# Qwiic_Adaptive_Switch_Input1_1.net
KiCad netlist of a schematic drawn in EAGLE
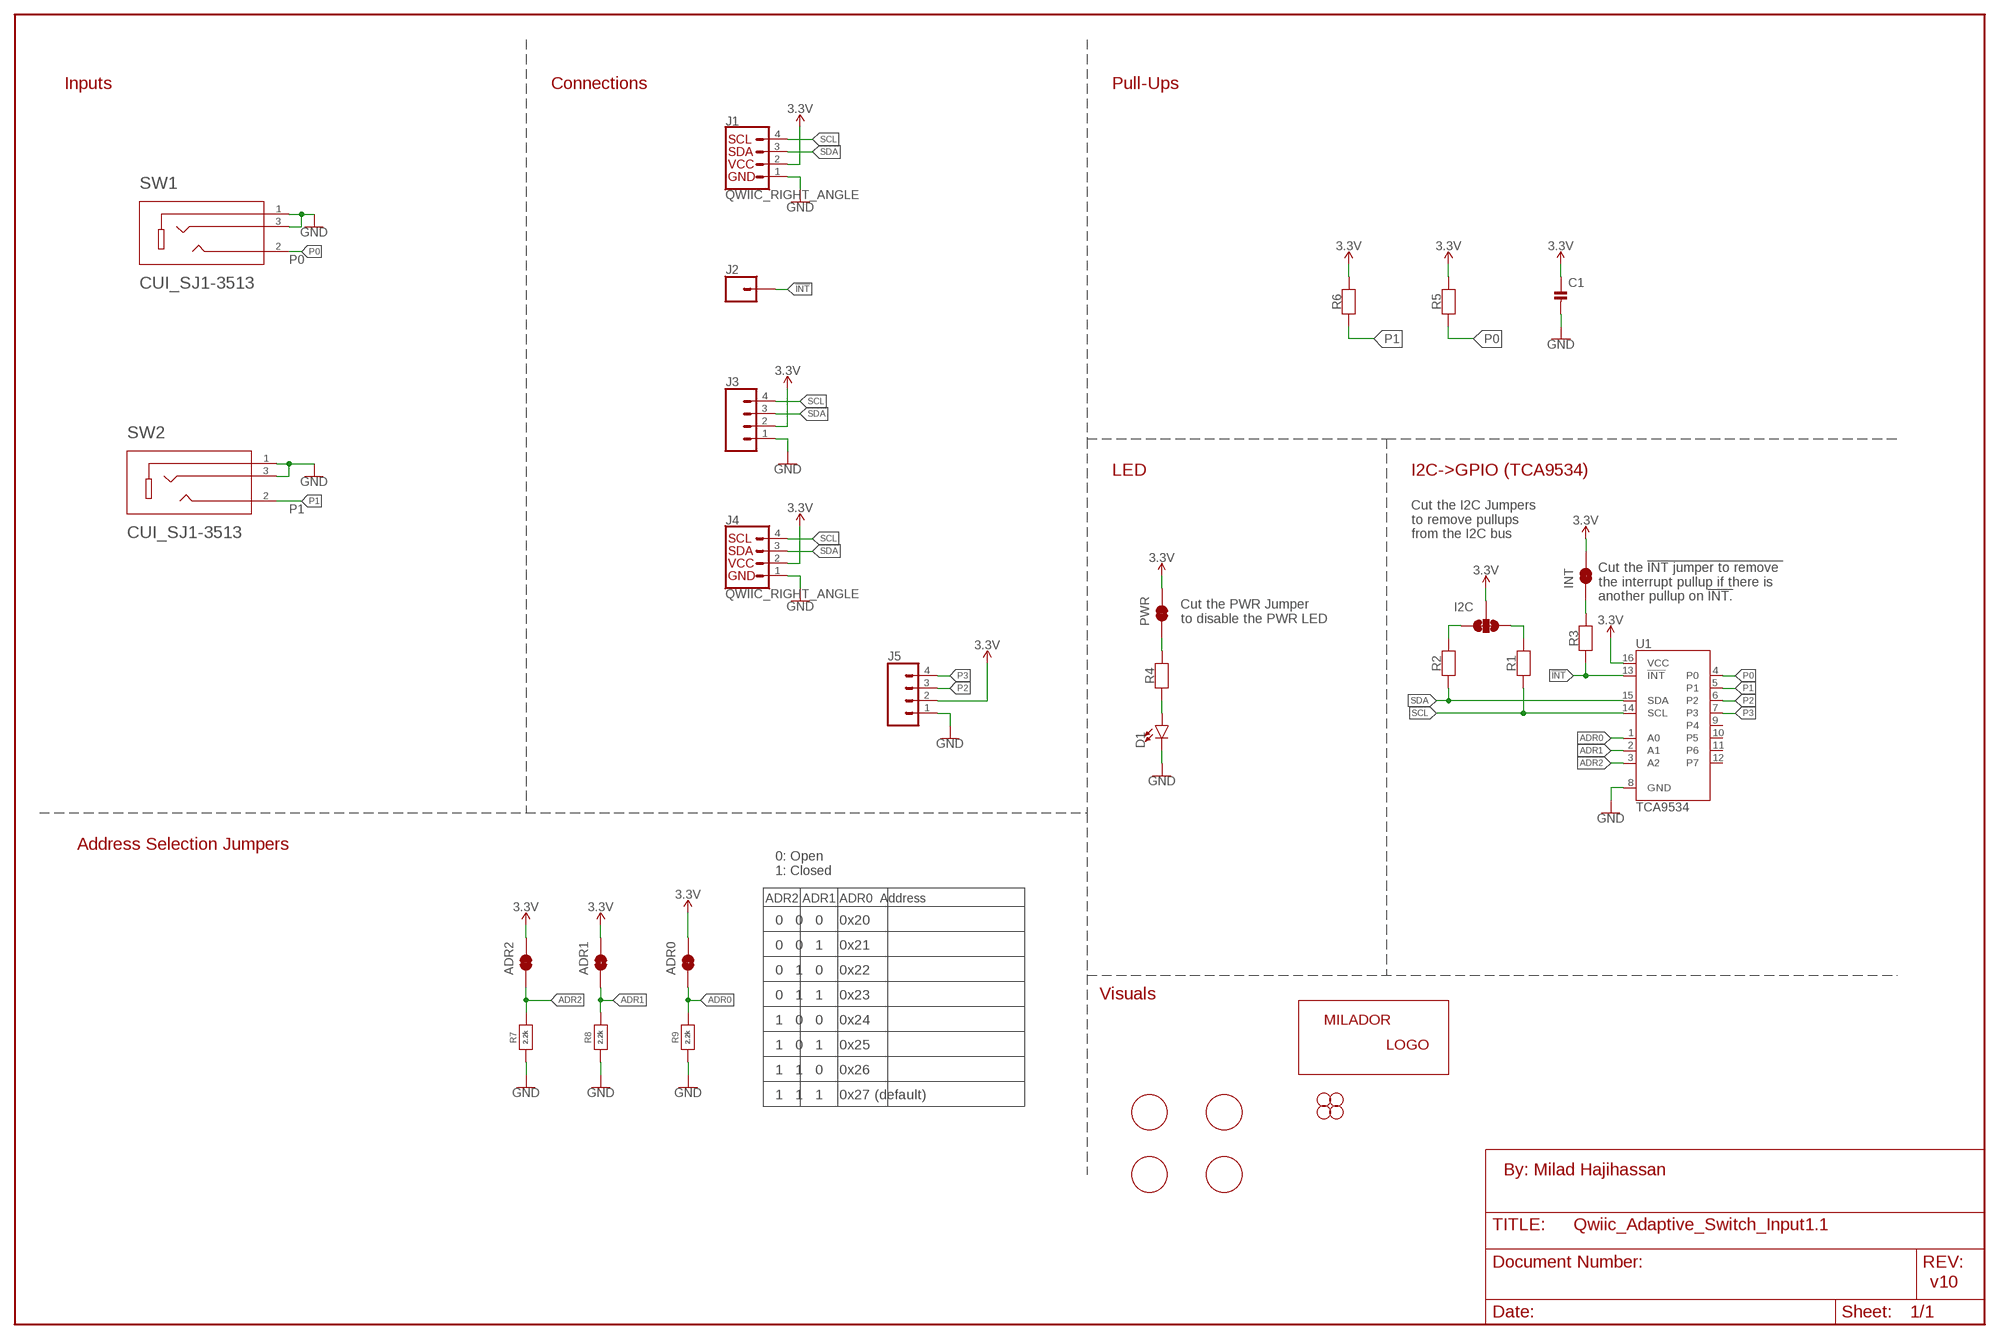
[diagram p0: schematic, sheet 1]

(export (version "E")
  (design (tool "Eeschema 10.0.6"))
  (components
    (comp (ref "ADR0")
      (value "JUMPERS-SMT_2_NC_TRACE_SILK")
      (footprint "eagle-import:JUMPERS_SMT-JUMPER_2_NC_TRACE_SILK")
      (libsource (lib "eagle-import") (part "JUMPERS-SMT_2_NC_TRACE_SILK"))
    )
    (comp (ref "ADR1")
      (value "JUMPERS-SMT_2_NC_TRACE_SILK")
      (footprint "eagle-import:JUMPERS_SMT-JUMPER_2_NC_TRACE_SILK")
      (libsource (lib "eagle-import") (part "JUMPERS-SMT_2_NC_TRACE_SILK"))
    )
    (comp (ref "ADR2")
      (value "JUMPERS-SMT_2_NC_TRACE_SILK")
      (footprint "eagle-import:JUMPERS_SMT-JUMPER_2_NC_TRACE_SILK")
      (libsource (lib "eagle-import") (part "JUMPERS-SMT_2_NC_TRACE_SILK"))
    )
    (comp (ref "C1")
      (value "0.1uF")
      (footprint "eagle-import:0805-MP")
      (libsource (lib "eagle-import") (part "CAP_CERAMIC-0805-MP"))
    )
    (comp (ref "D1")
      (value "RED")
      (footprint "eagle-import:CHIPLED_0805_NOOUTLINE")
      (libsource (lib "eagle-import") (part "LED0805_NOOUTLINE"))
    )
    (comp (ref "H1")
      (value "STAND-OFF-3.3")
      (footprint "eagle-import:STAND-OFF-3.3")
      (libsource (lib "eagle-import") (part "STAND-OFF-3.3"))
    )
    (comp (ref "H2")
      (value "STAND-OFF-3.3")
      (footprint "eagle-import:STAND-OFF-3.3")
      (libsource (lib "eagle-import") (part "STAND-OFF-3.3"))
    )
    (comp (ref "I2C")
      (value "JUMPERS_JUMPER-SMT_3_2-NC_TRACE_SILK")
      (footprint "eagle-import:JUMPERS_SMT-JUMPER_3_2-NC_TRACE_SILK")
      (libsource (lib "eagle-import") (part "JUMPERS_JUMPER-SMT_3_2-NC_TRACE_SILK"))
    )
    (comp (ref "INT")
      (value "JUMPERS-SMT_2_NC_TRACE_SILK")
      (footprint "eagle-import:JUMPERS_SMT-JUMPER_2_NC_TRACE_SILK")
      (libsource (lib "eagle-import") (part "JUMPERS-SMT_2_NC_TRACE_SILK"))
    )
    (comp (ref "J1")
      (value "QWIIC_RIGHT_ANGLE")
      (footprint "eagle-import:CONNECTORS_JST04_1MM_RA")
      (fields (field (name "PROD_ID") "CONN-13694"))
      (libsource (lib "eagle-import") (part "QWIIC_CONNECTORSJS-1MM"))
    )
    (comp (ref "J2")
      (value "CONNECTORS_CONN_01PTH_NO_SILK_YES_STOP")
      (footprint "eagle-import:CONNECTORS_1X01_NO_SILK")
      (libsource (lib "eagle-import") (part "CONNECTORS_CONN_01PTH_NO_SILK_YES_STOP"))
    )
    (comp (ref "J3")
      (value "CONNECTORS_CONN_041X04_NO_SILK")
      (footprint "eagle-import:CONNECTORS_1X04_NO_SILK")
      (libsource (lib "eagle-import") (part "CONNECTORS_CONN_041X04_NO_SILK"))
    )
    (comp (ref "J4")
      (value "QWIIC_RIGHT_ANGLE")
      (footprint "eagle-import:CONNECTORS_JST04_1MM_RA")
      (fields (field (name "PROD_ID") "CONN-13694"))
      (libsource (lib "eagle-import") (part "QWIIC_CONNECTORSJS-1MM"))
    )
    (comp (ref "J5")
      (value "CONNECTORS_CONN_041X04_NO_SILK")
      (footprint "eagle-import:CONNECTORS_1X04_NO_SILK")
      (libsource (lib "eagle-import") (part "CONNECTORS_CONN_041X04_NO_SILK"))
    )
    (comp (ref "JP3")
      (value "STAND-OFF-3.3")
      (footprint "eagle-import:STAND-OFF-3.3")
      (libsource (lib "eagle-import") (part "STAND-OFF-3.3"))
    )
    (comp (ref "JP4")
      (value "STAND-OFF-3.3")
      (footprint "eagle-import:STAND-OFF-3.3")
      (libsource (lib "eagle-import") (part "STAND-OFF-3.3"))
    )
    (comp (ref "LABEL_2")
      (value "MILADOR-SWITCH-NAME-SW1")
      (footprint "eagle-import:SWITCH-SW1")
      (libsource (lib "eagle-import") (part "MILADOR-SWITCH-NAME-SW1"))
    )
    (comp (ref "LABEL_3")
      (value "MILADOR-SWITCH-NAME-SW2")
      (footprint "eagle-import:SWITCH-SW2")
      (libsource (lib "eagle-import") (part "MILADOR-SWITCH-NAME-SW2"))
    )
    (comp (ref "LABEL_9")
      (value "MILADOR-SWITCH-NAME-SW-INPUT")
      (footprint "eagle-import:SWITCH-INPUT")
      (libsource (lib "eagle-import") (part "MILADOR-SWITCH-NAME-SW-INPUT"))
    )
    (comp (ref "LABEL_14")
      (value "MILADOR-LOGO-")
      (footprint "eagle-import:MILADOR_LOGO1")
      (libsource (lib "eagle-import") (part "MILADOR-LOGO-"))
    )
    (comp (ref "LABEL_18")
      (value "MILADOR-SWITCH-NAME-SW-INPUT")
      (footprint "eagle-import:SWITCH-INPUT")
      (libsource (lib "eagle-import") (part "MILADOR-SWITCH-NAME-SW-INPUT"))
    )
    (comp (ref "PWR")
      (value "JUMPERS-SMT_2_NC_TRACE_SILK")
      (footprint "eagle-import:JUMPERS_SMT-JUMPER_2_NC_TRACE_SILK")
      (libsource (lib "eagle-import") (part "JUMPERS-SMT_2_NC_TRACE_SILK"))
    )
    (comp (ref "R1")
      (value "2.2k")
      (footprint "eagle-import:0805-MP")
      (libsource (lib "eagle-import") (part "RESISTOR-0805-MP"))
    )
    (comp (ref "R2")
      (value "2.2k")
      (footprint "eagle-import:0805-MP")
      (libsource (lib "eagle-import") (part "RESISTOR-0805-MP"))
    )
    (comp (ref "R3")
      (value "10k")
      (footprint "eagle-import:0805-MP")
      (libsource (lib "eagle-import") (part "RESISTOR-0805-MP"))
    )
    (comp (ref "R4")
      (value "1k")
      (footprint "eagle-import:0805-MP")
      (libsource (lib "eagle-import") (part "RESISTOR-0805-MP"))
    )
    (comp (ref "R5")
      (value "4.7k")
      (footprint "eagle-import:0805-MP")
      (libsource (lib "eagle-import") (part "RESISTOR-0805-MP"))
    )
    (comp (ref "R6")
      (value "4.7K")
      (footprint "eagle-import:0805-MP")
      (libsource (lib "eagle-import") (part "RESISTOR-0805-MP"))
    )
    (comp (ref "R7")
      (value "2.2k")
      (footprint "eagle-import:0805-MP")
      (libsource (lib "eagle-import") (part "RESISTOR-0805-MP"))
    )
    (comp (ref "R8")
      (value "2.2k")
      (footprint "eagle-import:0805-MP")
      (libsource (lib "eagle-import") (part "RESISTOR-0805-MP"))
    )
    (comp (ref "R9")
      (value "2.2k")
      (footprint "eagle-import:0805-MP")
      (libsource (lib "eagle-import") (part "RESISTOR-0805-MP"))
    )
    (comp (ref "SW1")
      (value "CUI_SJ1-3513")
      (footprint "eagle-import:CUI_SJ1-3513")
      (libsource (lib "eagle-import") (part "CUI_SJ1-3513"))
    )
    (comp (ref "SW2")
      (value "CUI_SJ1-3513")
      (footprint "eagle-import:CUI_SJ1-3513")
      (libsource (lib "eagle-import") (part "CUI_SJ1-3513"))
    )
    (comp (ref "U1")
      (value "TCA9534")
      (footprint "eagle-import:16SOIC")
      (libsource (lib "eagle-import") (part "TCA9534U"))
    )
  )
  (nets
    (net (code "1") (name "/~{INT}") (class "Default")
      (node (ref "J2") (pin "1") (pinfunction "1_1") (pintype "passive"))
      (node (ref "R3") (pin "1") (pinfunction "1_1") (pintype "passive"))
      (node (ref "U1") (pin "13") (pinfunction "~{INT}_13") (pintype "bidirectional"))
    )
    (net (code "2") (name "3.3V") (class "Default")
      (node (ref "ADR0") (pin "2") (pinfunction "2_2") (pintype "passive"))
      (node (ref "ADR1") (pin "2") (pinfunction "2_2") (pintype "passive"))
      (node (ref "ADR2") (pin "2") (pinfunction "2_2") (pintype "passive"))
      (node (ref "C1") (pin "1") (pinfunction "1_1") (pintype "passive"))
      (node (ref "I2C") (pin "2") (pinfunction "2_2") (pintype "passive"))
      (node (ref "INT") (pin "2") (pinfunction "2_2") (pintype "passive"))
      (node (ref "J1") (pin "2") (pinfunction "2_2") (pintype "power_in"))
      (node (ref "J3") (pin "2") (pinfunction "2_2") (pintype "passive"))
      (node (ref "J4") (pin "2") (pinfunction "2_2") (pintype "power_in"))
      (node (ref "J5") (pin "2") (pinfunction "2_2") (pintype "passive"))
      (node (ref "PWR") (pin "2") (pinfunction "2_2") (pintype "passive"))
      (node (ref "R5") (pin "2") (pinfunction "2_2") (pintype "passive"))
      (node (ref "R6") (pin "2") (pinfunction "2_2") (pintype "passive"))
      (node (ref "U1") (pin "16") (pinfunction "VCC_16") (pintype "bidirectional"))
    )
    (net (code "3") (name "ADR0") (class "Default")
      (node (ref "ADR0") (pin "1") (pinfunction "1_1") (pintype "passive"))
      (node (ref "R9") (pin "2") (pinfunction "2_2") (pintype "passive"))
      (node (ref "U1") (pin "1") (pinfunction "A0_1") (pintype "bidirectional"))
    )
    (net (code "4") (name "ADR1") (class "Default")
      (node (ref "ADR1") (pin "1") (pinfunction "1_1") (pintype "passive"))
      (node (ref "R8") (pin "2") (pinfunction "2_2") (pintype "passive"))
      (node (ref "U1") (pin "2") (pinfunction "A1_2") (pintype "bidirectional"))
    )
    (net (code "5") (name "ADR2") (class "Default")
      (node (ref "ADR2") (pin "1") (pinfunction "1_1") (pintype "passive"))
      (node (ref "R7") (pin "2") (pinfunction "2_2") (pintype "passive"))
      (node (ref "U1") (pin "3") (pinfunction "A2_3") (pintype "bidirectional"))
    )
    (net (code "6") (name "GND") (class "Default")
      (node (ref "C1") (pin "2") (pinfunction "2_2") (pintype "passive"))
      (node (ref "D1") (pin "C") (pinfunction "C_C") (pintype "passive"))
      (node (ref "J1") (pin "1") (pinfunction "1_1") (pintype "power_in"))
      (node (ref "J3") (pin "1") (pinfunction "1_1") (pintype "passive"))
      (node (ref "J4") (pin "1") (pinfunction "1_1") (pintype "power_in"))
      (node (ref "J5") (pin "1") (pinfunction "1_1") (pintype "passive"))
      (node (ref "R7") (pin "1") (pinfunction "1_1") (pintype "passive"))
      (node (ref "R8") (pin "1") (pinfunction "1_1") (pintype "passive"))
      (node (ref "R9") (pin "1") (pinfunction "1_1") (pintype "passive"))
      (node (ref "SW1") (pin "1") (pinfunction "1_1") (pintype "passive"))
      (node (ref "SW1") (pin "3") (pinfunction "3_3") (pintype "passive"))
      (node (ref "SW2") (pin "1") (pinfunction "1_1") (pintype "passive"))
      (node (ref "SW2") (pin "3") (pinfunction "3_3") (pintype "passive"))
      (node (ref "U1") (pin "8") (pinfunction "GND_8") (pintype "bidirectional"))
    )
    (net (code "7") (name "Net-(D1-PadA)") (class "Default")
      (node (ref "D1") (pin "A") (pinfunction "A_A") (pintype "passive"))
      (node (ref "R4") (pin "1") (pinfunction "1_1") (pintype "passive"))
    )
    (net (code "8") (name "Net-(I2C-Pad1)") (class "Default")
      (node (ref "I2C") (pin "1") (pinfunction "1_1") (pintype "passive"))
      (node (ref "R2") (pin "2") (pinfunction "2_2") (pintype "passive"))
    )
    (net (code "9") (name "Net-(I2C-Pad3)") (class "Default")
      (node (ref "I2C") (pin "3") (pinfunction "3_3") (pintype "passive"))
      (node (ref "R1") (pin "2") (pinfunction "2_2") (pintype "passive"))
    )
    (net (code "10") (name "Net-(INT-Pad1)") (class "Default")
      (node (ref "INT") (pin "1") (pinfunction "1_1") (pintype "passive"))
      (node (ref "R3") (pin "2") (pinfunction "2_2") (pintype "passive"))
    )
    (net (code "11") (name "Net-(PWR-Pad1)") (class "Default")
      (node (ref "PWR") (pin "1") (pinfunction "1_1") (pintype "passive"))
      (node (ref "R4") (pin "2") (pinfunction "2_2") (pintype "passive"))
    )
    (net (code "12") (name "P0") (class "Default")
      (node (ref "R5") (pin "1") (pinfunction "1_1") (pintype "passive"))
      (node (ref "SW1") (pin "2") (pinfunction "2_2") (pintype "passive"))
      (node (ref "U1") (pin "4") (pinfunction "P0_4") (pintype "bidirectional"))
    )
    (net (code "13") (name "P1") (class "Default")
      (node (ref "R6") (pin "1") (pinfunction "1_1") (pintype "passive"))
      (node (ref "SW2") (pin "2") (pinfunction "2_2") (pintype "passive"))
      (node (ref "U1") (pin "5") (pinfunction "P1_5") (pintype "bidirectional"))
    )
    (net (code "14") (name "P2") (class "Default")
      (node (ref "J5") (pin "3") (pinfunction "3_3") (pintype "passive"))
      (node (ref "U1") (pin "6") (pinfunction "P2_6") (pintype "bidirectional"))
    )
    (net (code "15") (name "P3") (class "Default")
      (node (ref "J5") (pin "4") (pinfunction "4_4") (pintype "passive"))
      (node (ref "U1") (pin "7") (pinfunction "P3_7") (pintype "bidirectional"))
    )
    (net (code "16") (name "SCL") (class "Default")
      (node (ref "J1") (pin "4") (pinfunction "4_4") (pintype "passive"))
      (node (ref "J3") (pin "4") (pinfunction "4_4") (pintype "passive"))
      (node (ref "J4") (pin "4") (pinfunction "4_4") (pintype "passive"))
      (node (ref "R1") (pin "1") (pinfunction "1_1") (pintype "passive"))
      (node (ref "U1") (pin "14") (pinfunction "SCL_14") (pintype "bidirectional"))
    )
    (net (code "17") (name "SDA") (class "Default")
      (node (ref "J1") (pin "3") (pinfunction "3_3") (pintype "passive"))
      (node (ref "J3") (pin "3") (pinfunction "3_3") (pintype "passive"))
      (node (ref "J4") (pin "3") (pinfunction "3_3") (pintype "passive"))
      (node (ref "R2") (pin "1") (pinfunction "1_1") (pintype "passive"))
      (node (ref "U1") (pin "15") (pinfunction "SDA_15") (pintype "bidirectional"))
    )
    (net (code "18") (name "unconnected-(U1-P4-Pad9)") (class "Default")
      (node (ref "U1") (pin "9") (pinfunction "P4_9") (pintype "bidirectional"))
    )
    (net (code "19") (name "unconnected-(U1-P5-Pad10)") (class "Default")
      (node (ref "U1") (pin "10") (pinfunction "P5_10") (pintype "bidirectional"))
    )
    (net (code "20") (name "unconnected-(U1-P6-Pad11)") (class "Default")
      (node (ref "U1") (pin "11") (pinfunction "P6_11") (pintype "bidirectional"))
    )
    (net (code "21") (name "unconnected-(U1-P7-Pad12)") (class "Default")
      (node (ref "U1") (pin "12") (pinfunction "P7_12") (pintype "bidirectional"))
    )
  )
)
